# Blinky.net
KiCad netlist of a schematic drawn in EAGLE
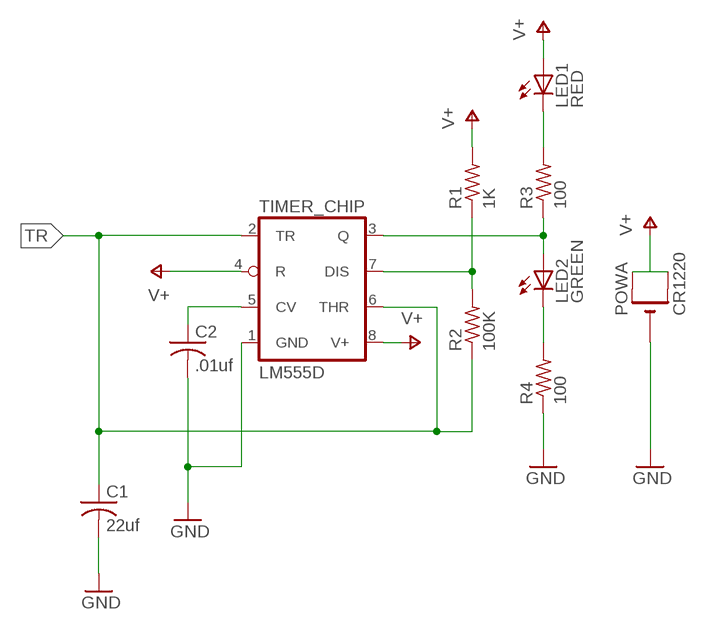
[diagram p0: schematic, sheet 1]

(export (version "E")
  (design (tool "Eeschema 10.0.6"))
  (components
    (comp (ref "C1")
      (value "22uf")
      (footprint "eagle-import:C0805")
      (fields (field (name "MF") "AVX") (field (name "MPN") "08056D226MAT2A"))
      (libsource (lib "eagle-import") (part "C-USC0805"))
    )
    (comp (ref "C2")
      (value ".01uf")
      (footprint "eagle-import:C0805")
      (fields (field (name "MF") "AVX") (field (name "MPN") "08051A101J4T4A"))
      (libsource (lib "eagle-import") (part "C-USC0805"))
    )
    (comp (ref "LED1")
      (value "RED")
      (footprint "eagle-import:CHIP-LED0805")
      (fields (field (name "MF") "MULTICOMP") (field (name "MPN") "MCL-S270SRC"))
      (libsource (lib "eagle-import") (part "LEDCHIP-LED0805"))
    )
    (comp (ref "LED2")
      (value "GREEN")
      (footprint "eagle-import:CHIP-LED0805")
      (fields (field (name "MF") "MULTICOMP") (field (name "MPN") "OVS-0804"))
      (libsource (lib "eagle-import") (part "LEDCHIP-LED0805"))
    )
    (comp (ref "POWA")
      (value "CR1220")
      (footprint "eagle-import:CR1220-SMD")
      (fields (field (name "MF") "HARWIN") (field (name "MPN") "S8411-45R"))
      (libsource (lib "eagle-import") (part "CR1220SMT"))
    )
    (comp (ref "R1")
      (value "1K")
      (footprint "eagle-import:R0805")
      (fields (field (name "MF") "VISHAY") (field (name "MPN") "CRCW08051K00FKTA"))
      (libsource (lib "eagle-import") (part "R-US_R0805"))
    )
    (comp (ref "R2")
      (value "100K")
      (footprint "eagle-import:R0805")
      (fields (field (name "MF") "VISHAY") (field (name "MPN") "CRCW0805100KFKTA"))
      (libsource (lib "eagle-import") (part "R-US_R0805"))
    )
    (comp (ref "R3")
      (value "100")
      (footprint "eagle-import:R0805")
      (fields (field (name "MF") "VISHAY") (field (name "MPN") "CRCW0805100RFKTA"))
      (libsource (lib "eagle-import") (part "R-US_R0805"))
    )
    (comp (ref "R4")
      (value "100")
      (footprint "eagle-import:R0805")
      (fields (field (name "MF") "VISHAY") (field (name "MPN") "CRCW0805100RFKTA"))
      (libsource (lib "eagle-import") (part "R-US_R0805"))
    )
    (comp (ref "TIMER_CHIP")
      (value "LM555D")
      (footprint "eagle-import:SO08")
      (fields (field (name "MF") "TEXAS INSTRUMENTS") (field (name "MPN") "SA555D"))
      (libsource (lib "eagle-import") (part "555DLM"))
    )
  )
  (nets
    (net (code "1") (name "GND") (class "Default")
      (node (ref "C1") (pin "2") (pinfunction "2_2") (pintype "passive"))
      (node (ref "C2") (pin "2") (pinfunction "2_2") (pintype "passive"))
      (node (ref "POWA") (pin "-") (pinfunction "-_-") (pintype "passive"))
      (node (ref "R4") (pin "1") (pinfunction "1_1") (pintype "passive"))
      (node (ref "TIMER_CHIP") (pin "1") (pinfunction "GND_1") (pintype "power_in"))
    )
    (net (code "2") (name "Net-(LED1-PadC)") (class "Default")
      (node (ref "LED1") (pin "C") (pinfunction "C_C") (pintype "passive"))
      (node (ref "R3") (pin "2") (pinfunction "2_2") (pintype "passive"))
    )
    (net (code "3") (name "Net-(LED2-PadC)") (class "Default")
      (node (ref "LED2") (pin "C") (pinfunction "C_C") (pintype "passive"))
      (node (ref "R4") (pin "2") (pinfunction "2_2") (pintype "passive"))
    )
    (net (code "4") (name "Net-(TIMER_CHIP-CV)") (class "Default")
      (node (ref "C2") (pin "1") (pinfunction "1_1") (pintype "passive"))
      (node (ref "TIMER_CHIP") (pin "5") (pinfunction "CV_5") (pintype "input"))
    )
    (net (code "5") (name "Net-(TIMER_CHIP-DIS)") (class "Default")
      (node (ref "R1") (pin "1") (pinfunction "1_1") (pintype "passive"))
      (node (ref "R2") (pin "2") (pinfunction "2_2") (pintype "passive"))
      (node (ref "TIMER_CHIP") (pin "7") (pinfunction "DIS_7") (pintype "input"))
    )
    (net (code "6") (name "Net-(TIMER_CHIP-Q)") (class "Default")
      (node (ref "LED2") (pin "A") (pinfunction "A_A") (pintype "passive"))
      (node (ref "R3") (pin "1") (pinfunction "1_1") (pintype "passive"))
      (node (ref "TIMER_CHIP") (pin "3") (pinfunction "Q_3") (pintype "output"))
    )
    (net (code "7") (name "TR") (class "Default")
      (node (ref "C1") (pin "1") (pinfunction "1_1") (pintype "passive"))
      (node (ref "R2") (pin "1") (pinfunction "1_1") (pintype "passive"))
      (node (ref "TIMER_CHIP") (pin "2") (pinfunction "TR_2") (pintype "input"))
      (node (ref "TIMER_CHIP") (pin "6") (pinfunction "THR_6") (pintype "input"))
    )
    (net (code "8") (name "V+") (class "Default")
      (node (ref "LED1") (pin "A") (pinfunction "A_A") (pintype "passive"))
      (node (ref "POWA") (pin "+$1") (pinfunction "+_+$1") (pintype "passive"))
      (node (ref "POWA") (pin "+$2") (pinfunction "+1_+$2") (pintype "passive"))
      (node (ref "R1") (pin "2") (pinfunction "2_2") (pintype "passive"))
      (node (ref "TIMER_CHIP") (pin "4") (pinfunction "R_4") (pintype "input"))
      (node (ref "TIMER_CHIP") (pin "8") (pinfunction "V+_8") (pintype "power_in"))
    )
  )
)
